# Grove_-_Tricks_v1_0.net
KiCad netlist of a schematic drawn in EAGLE
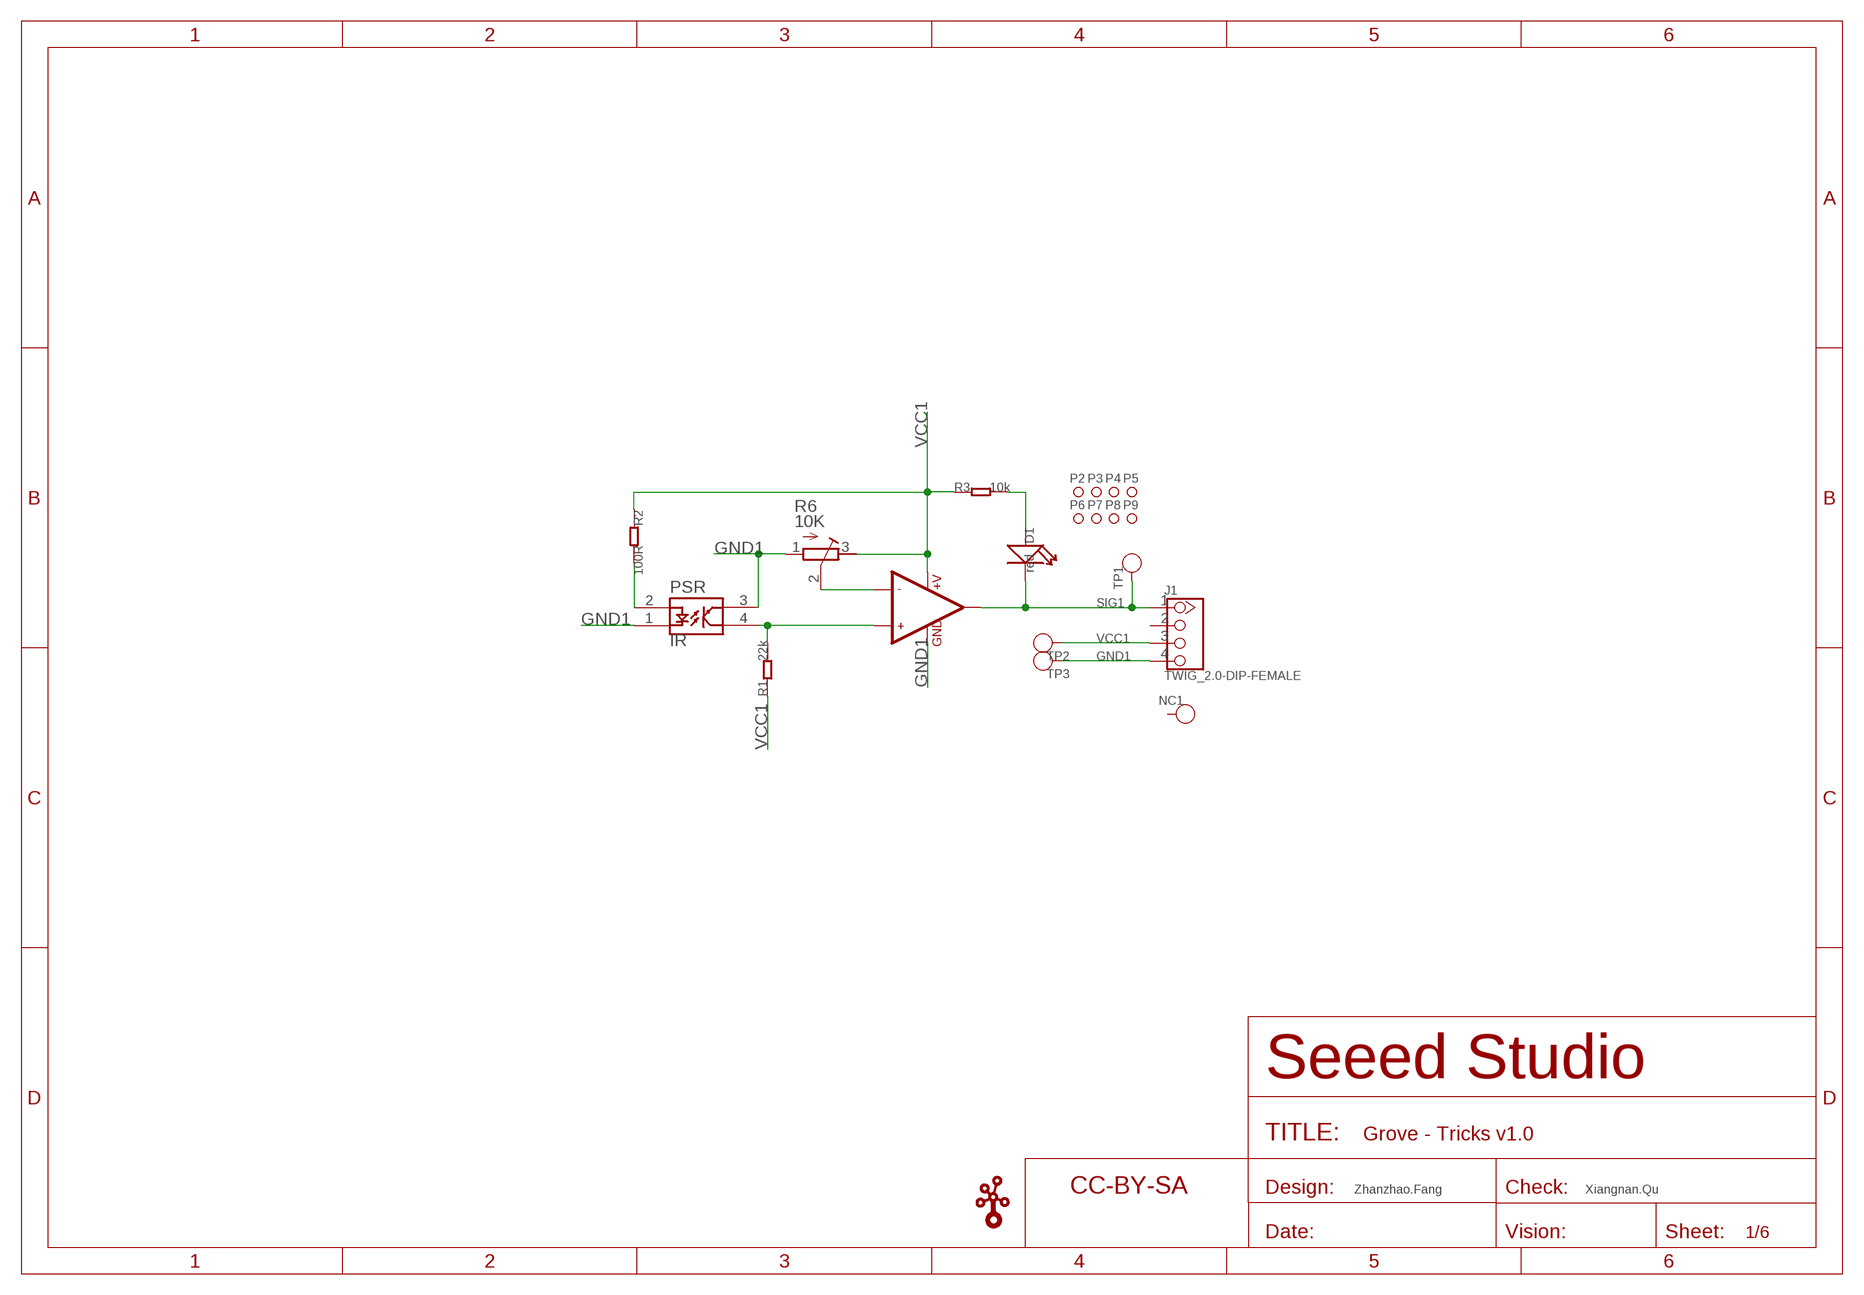
[diagram p0: schematic, sheet 1]
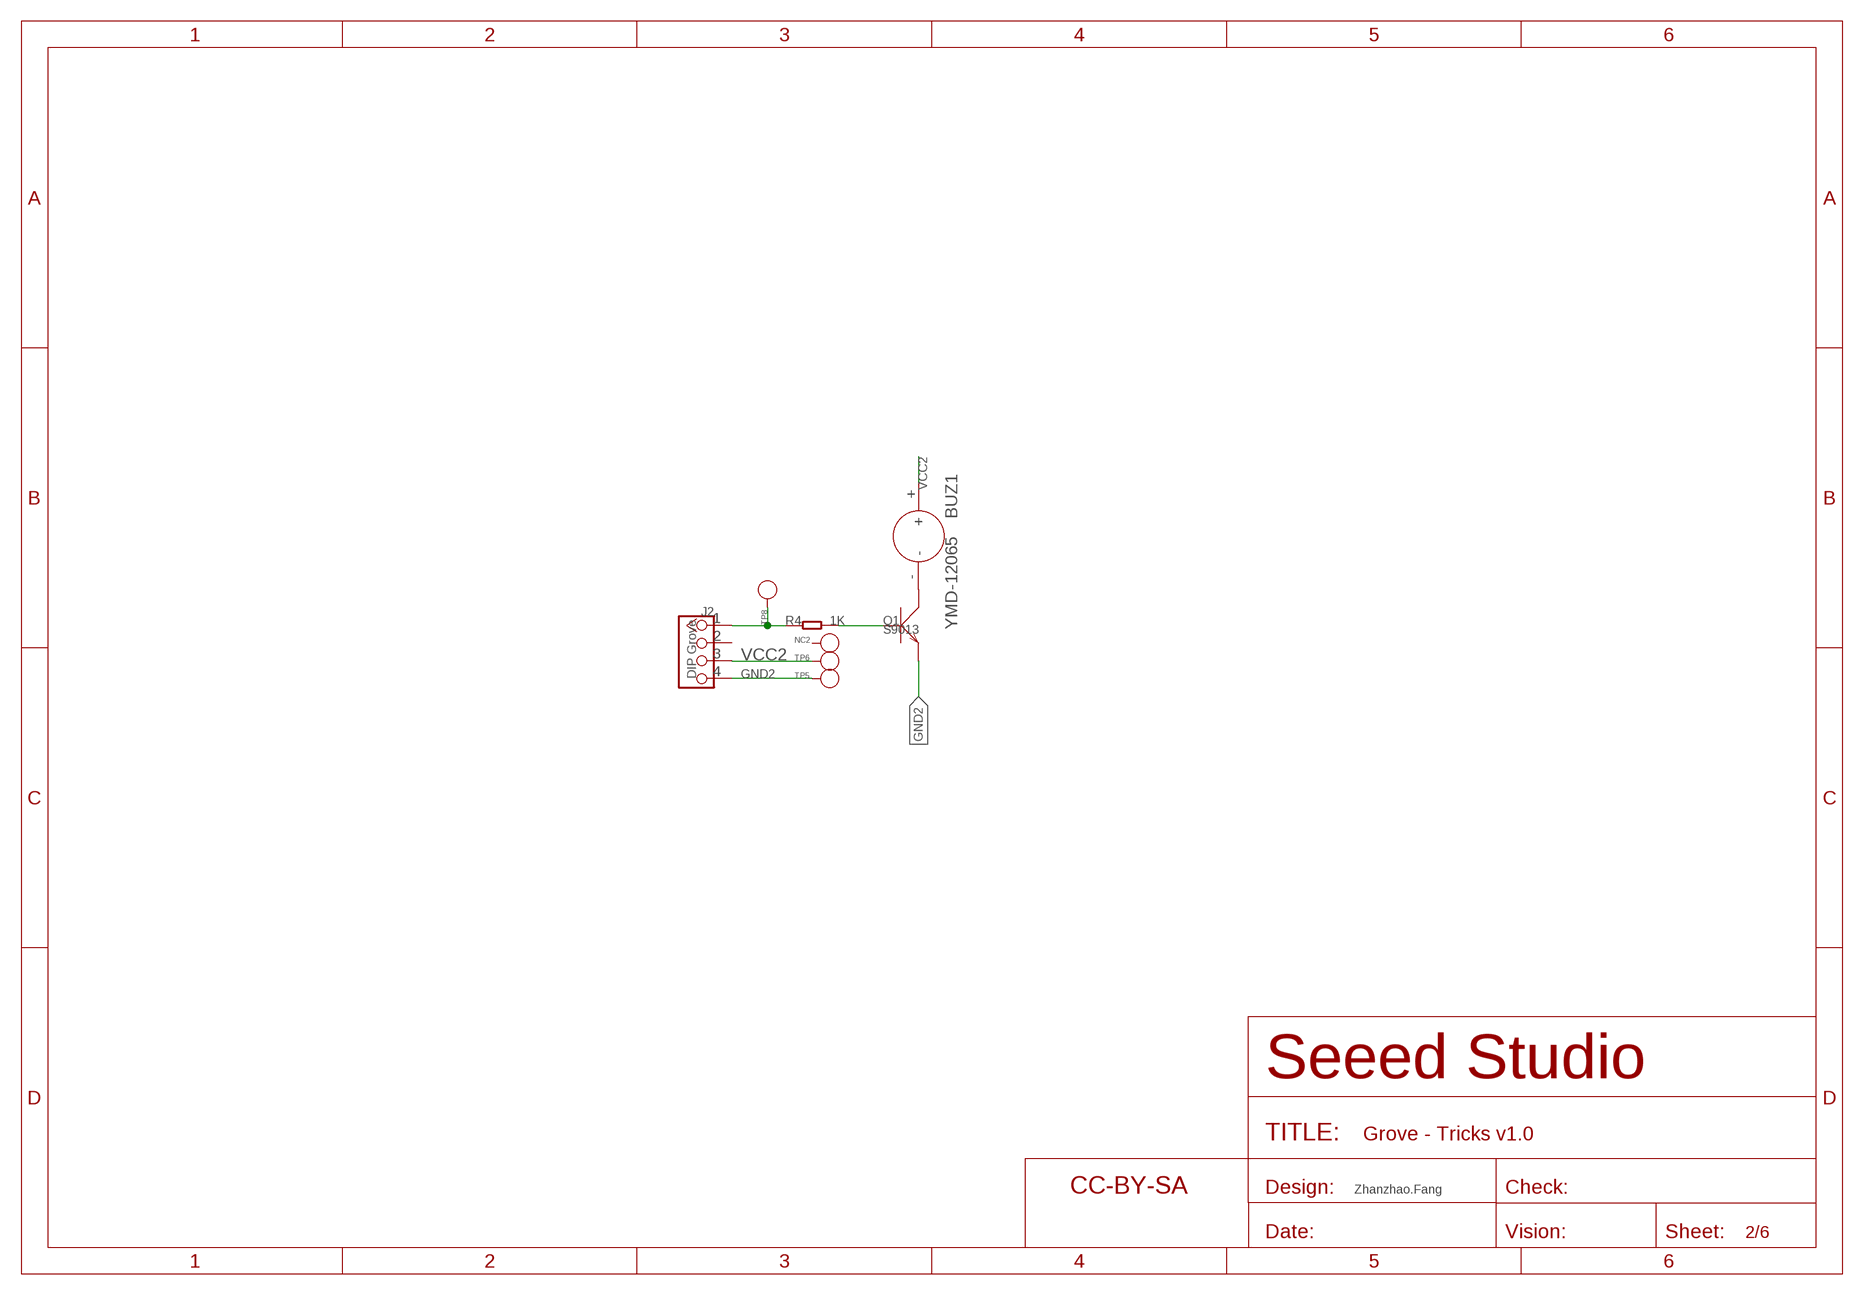
[diagram p1: schematic, sheet 2]
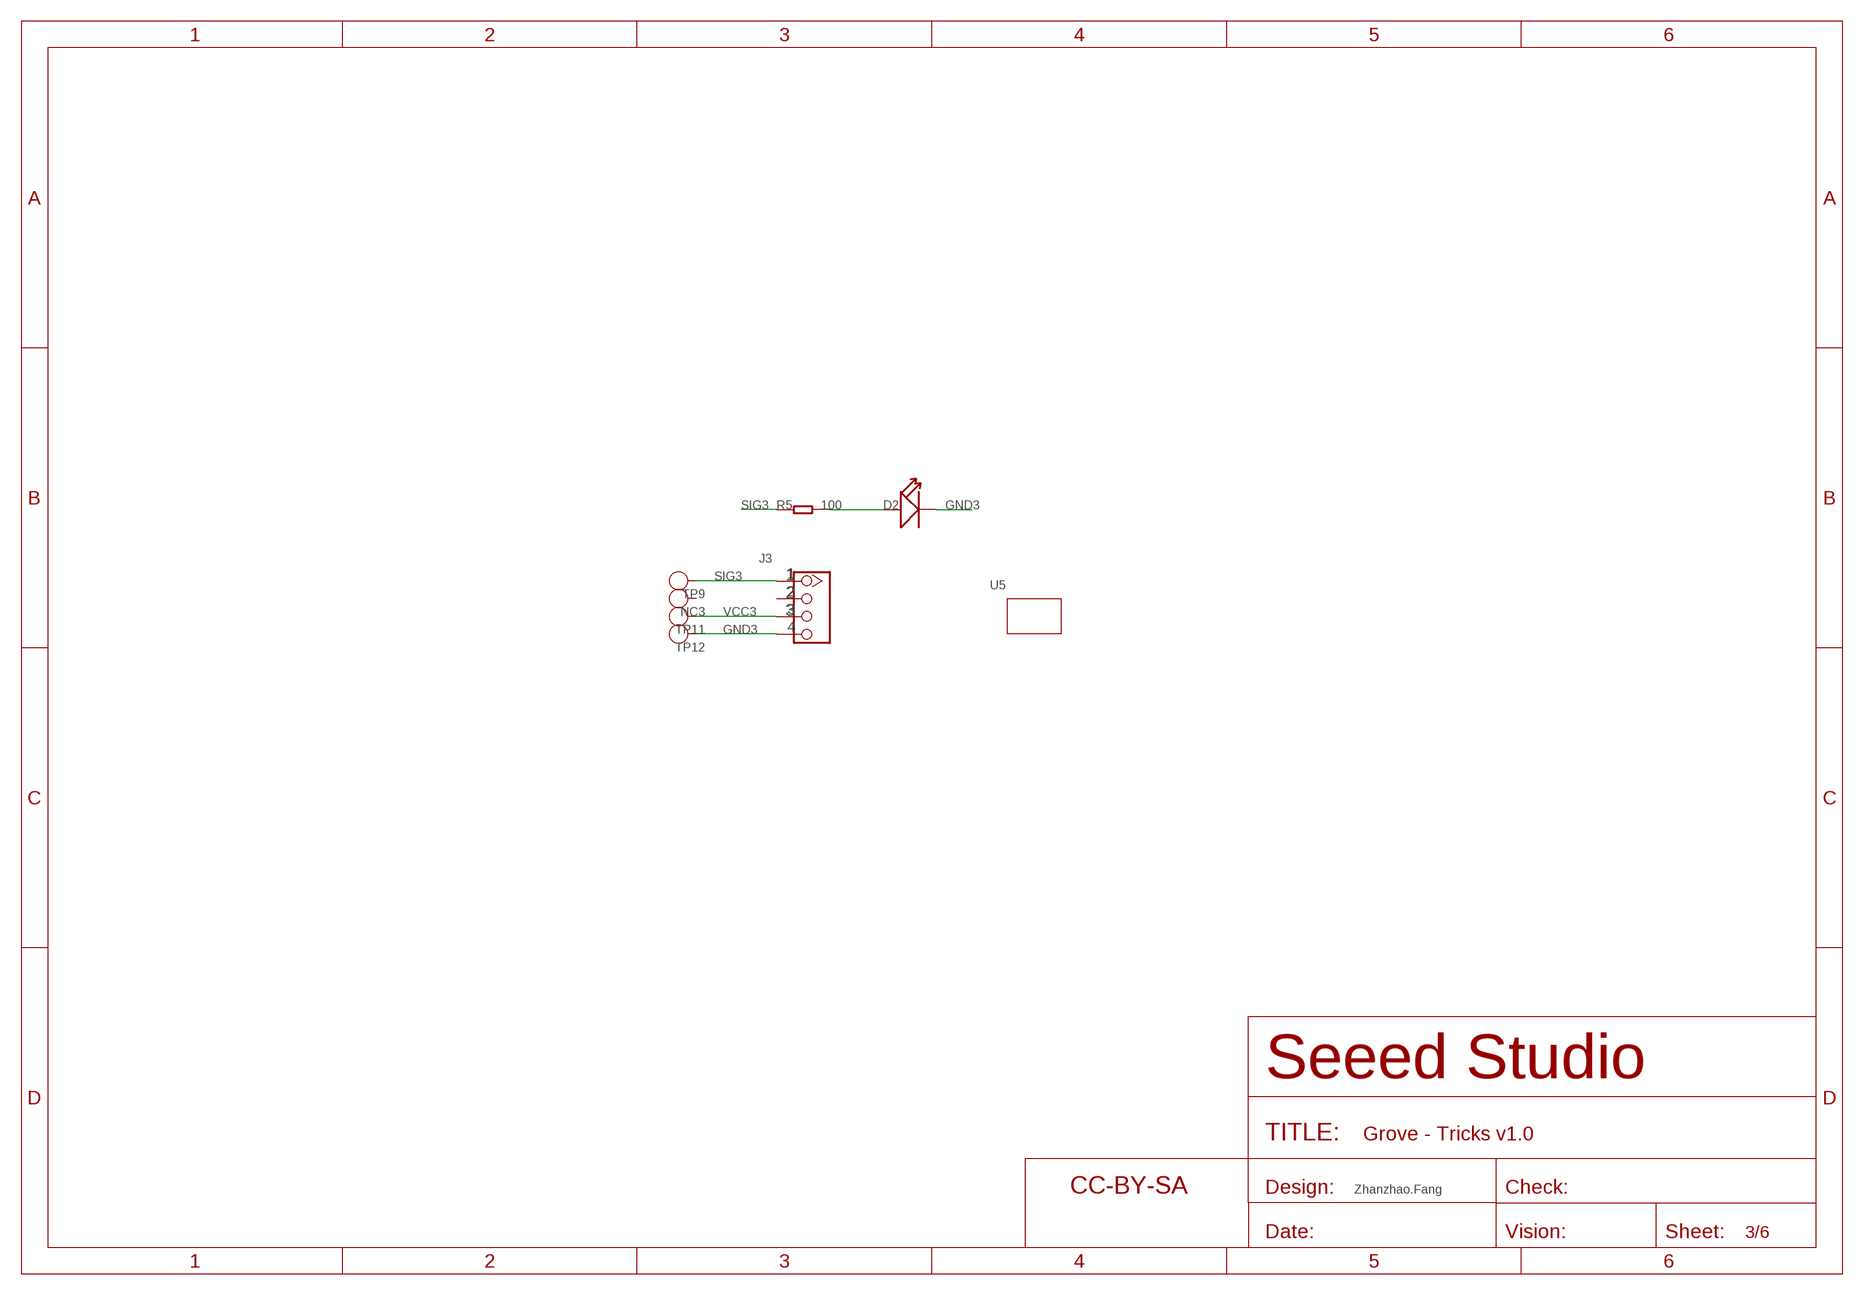
[diagram p2: schematic, sheet 3]
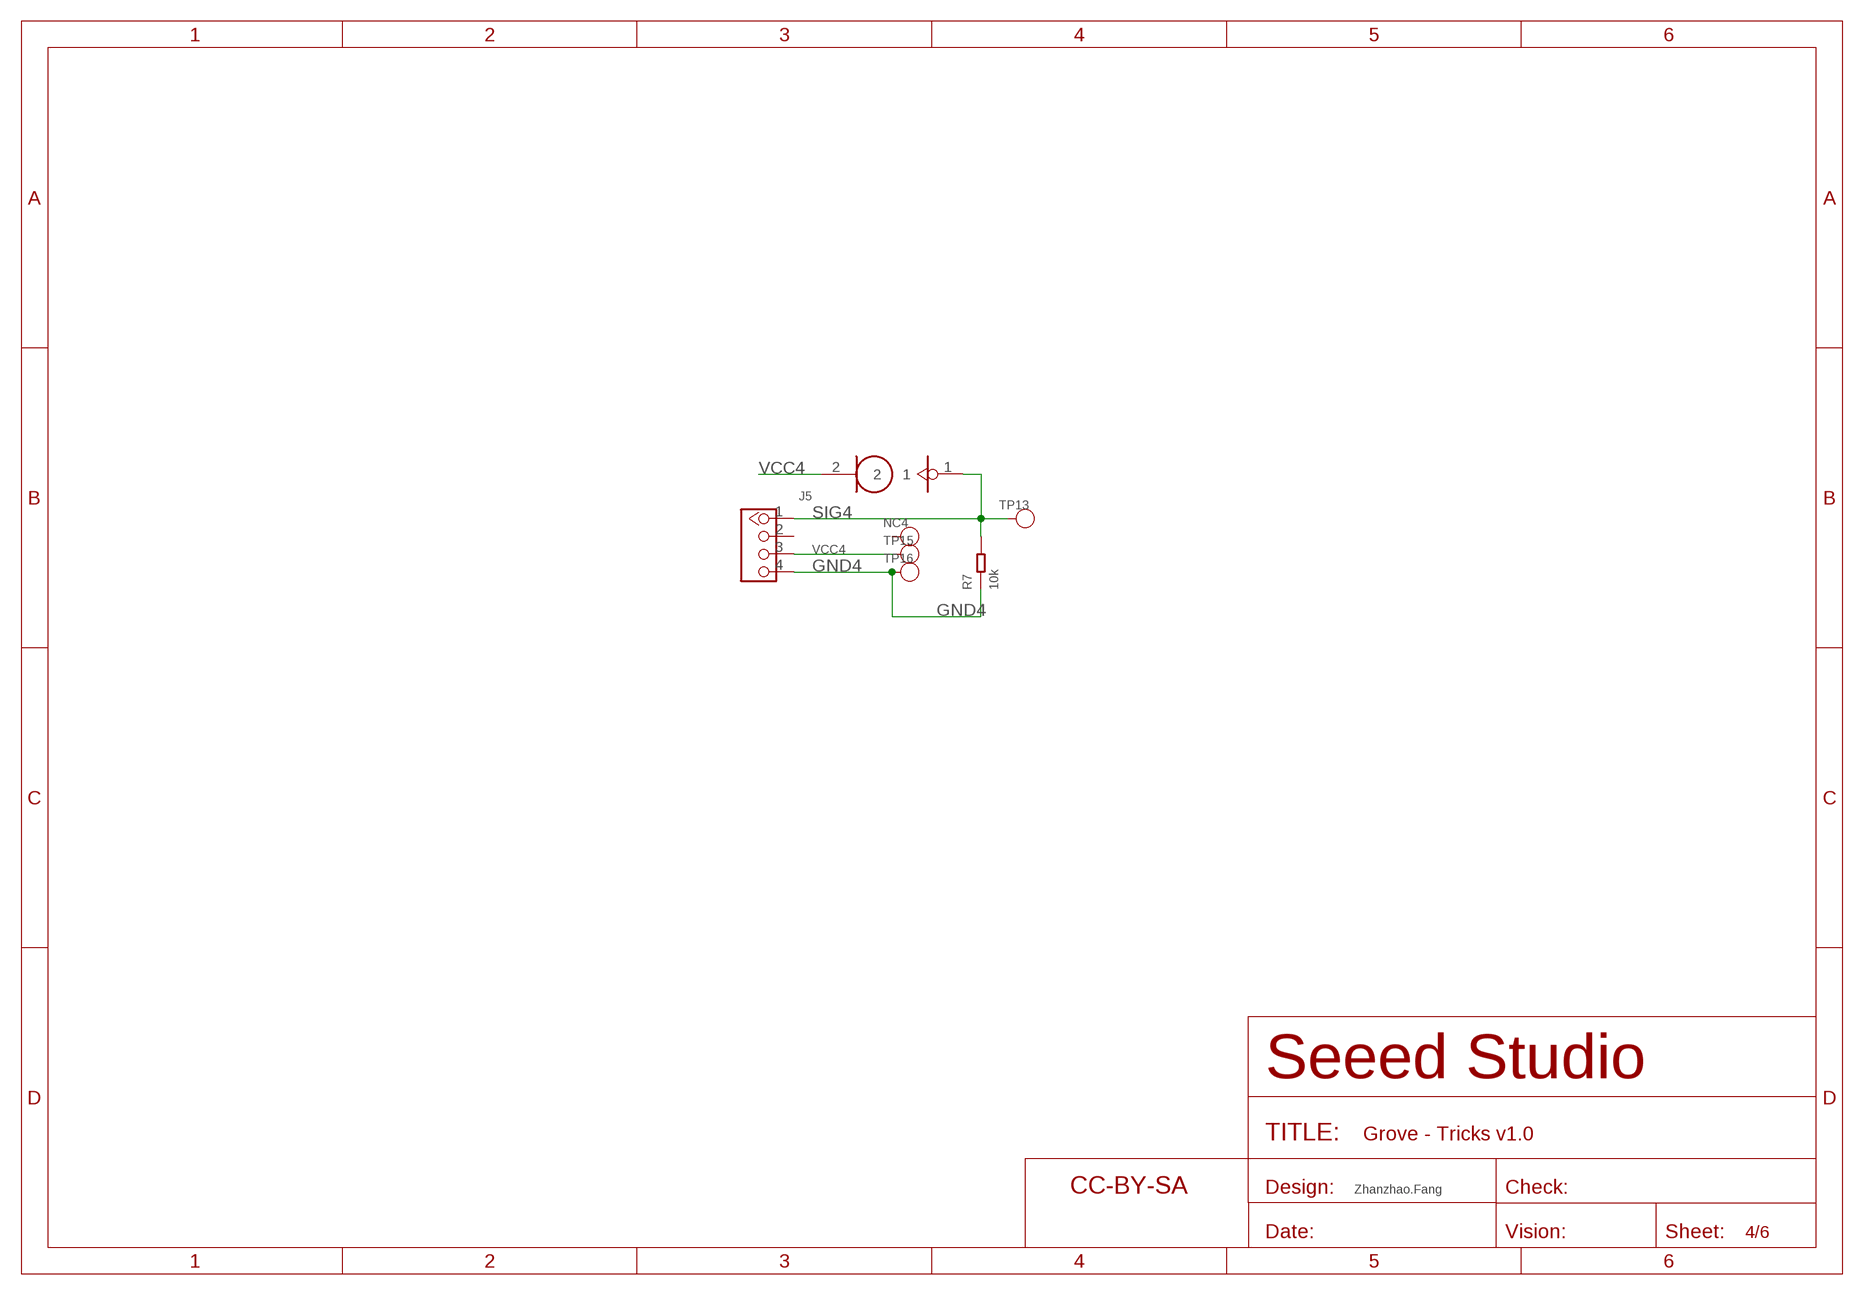
[diagram p3: schematic, sheet 4]
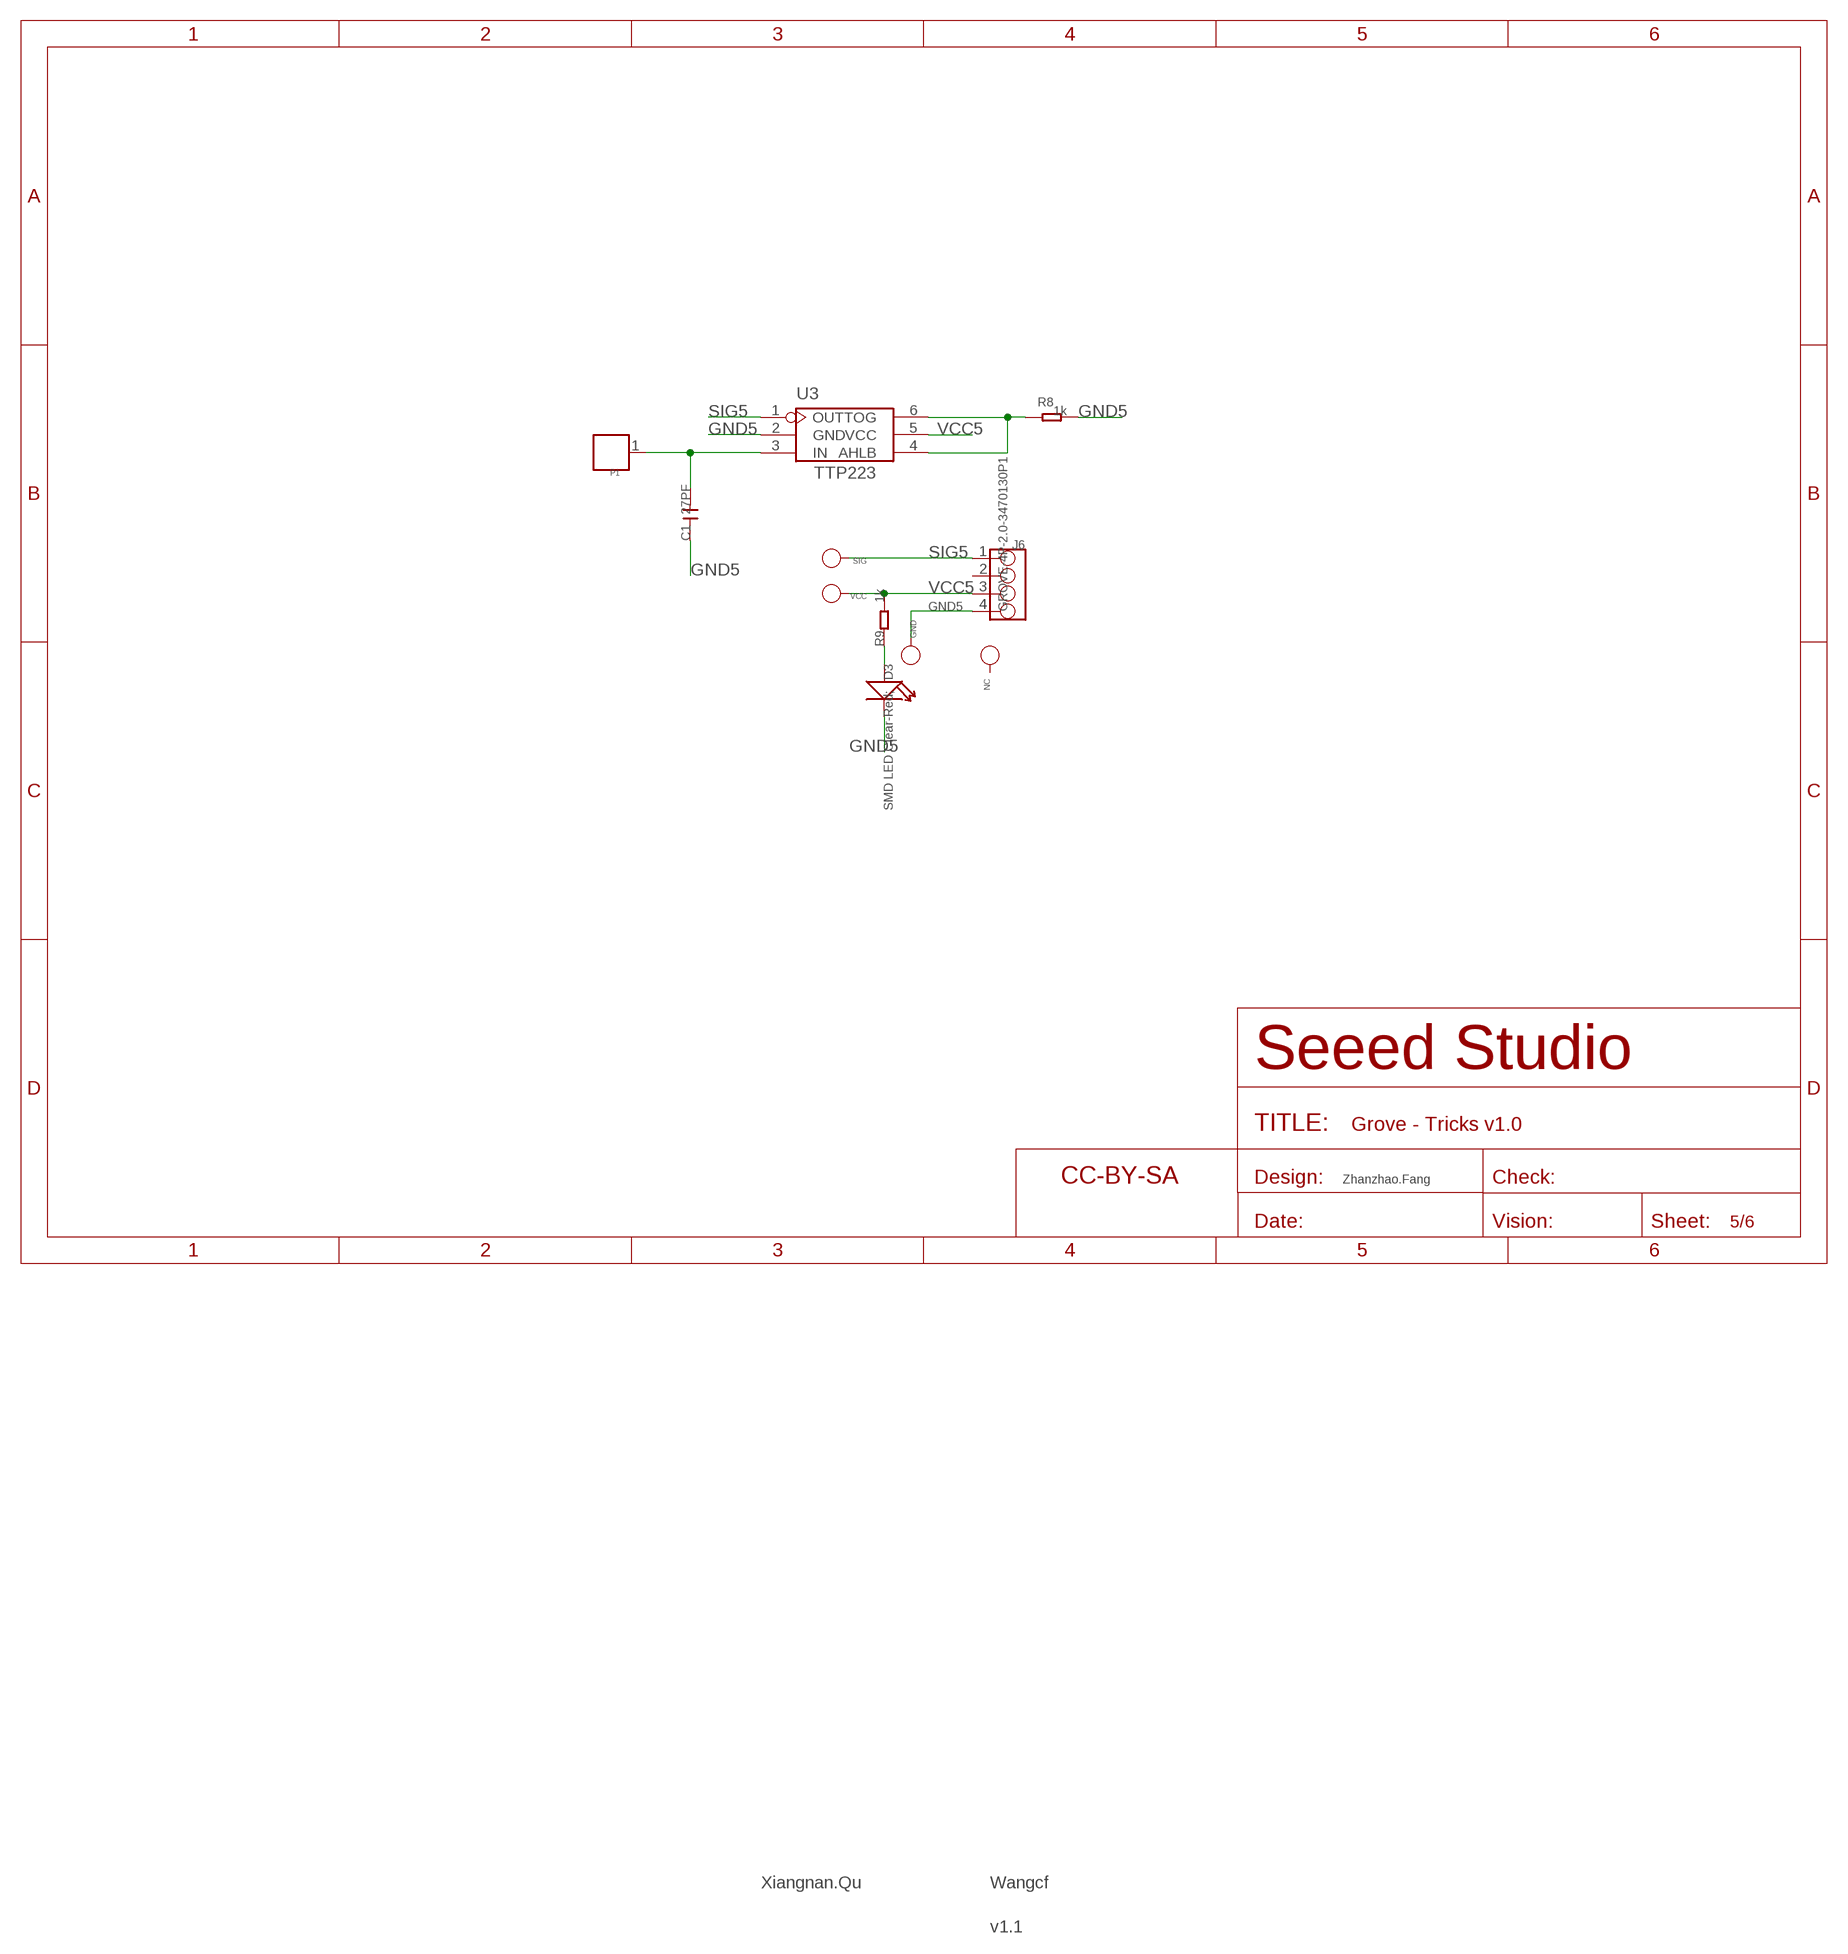
[diagram p4: schematic, sheet 5]
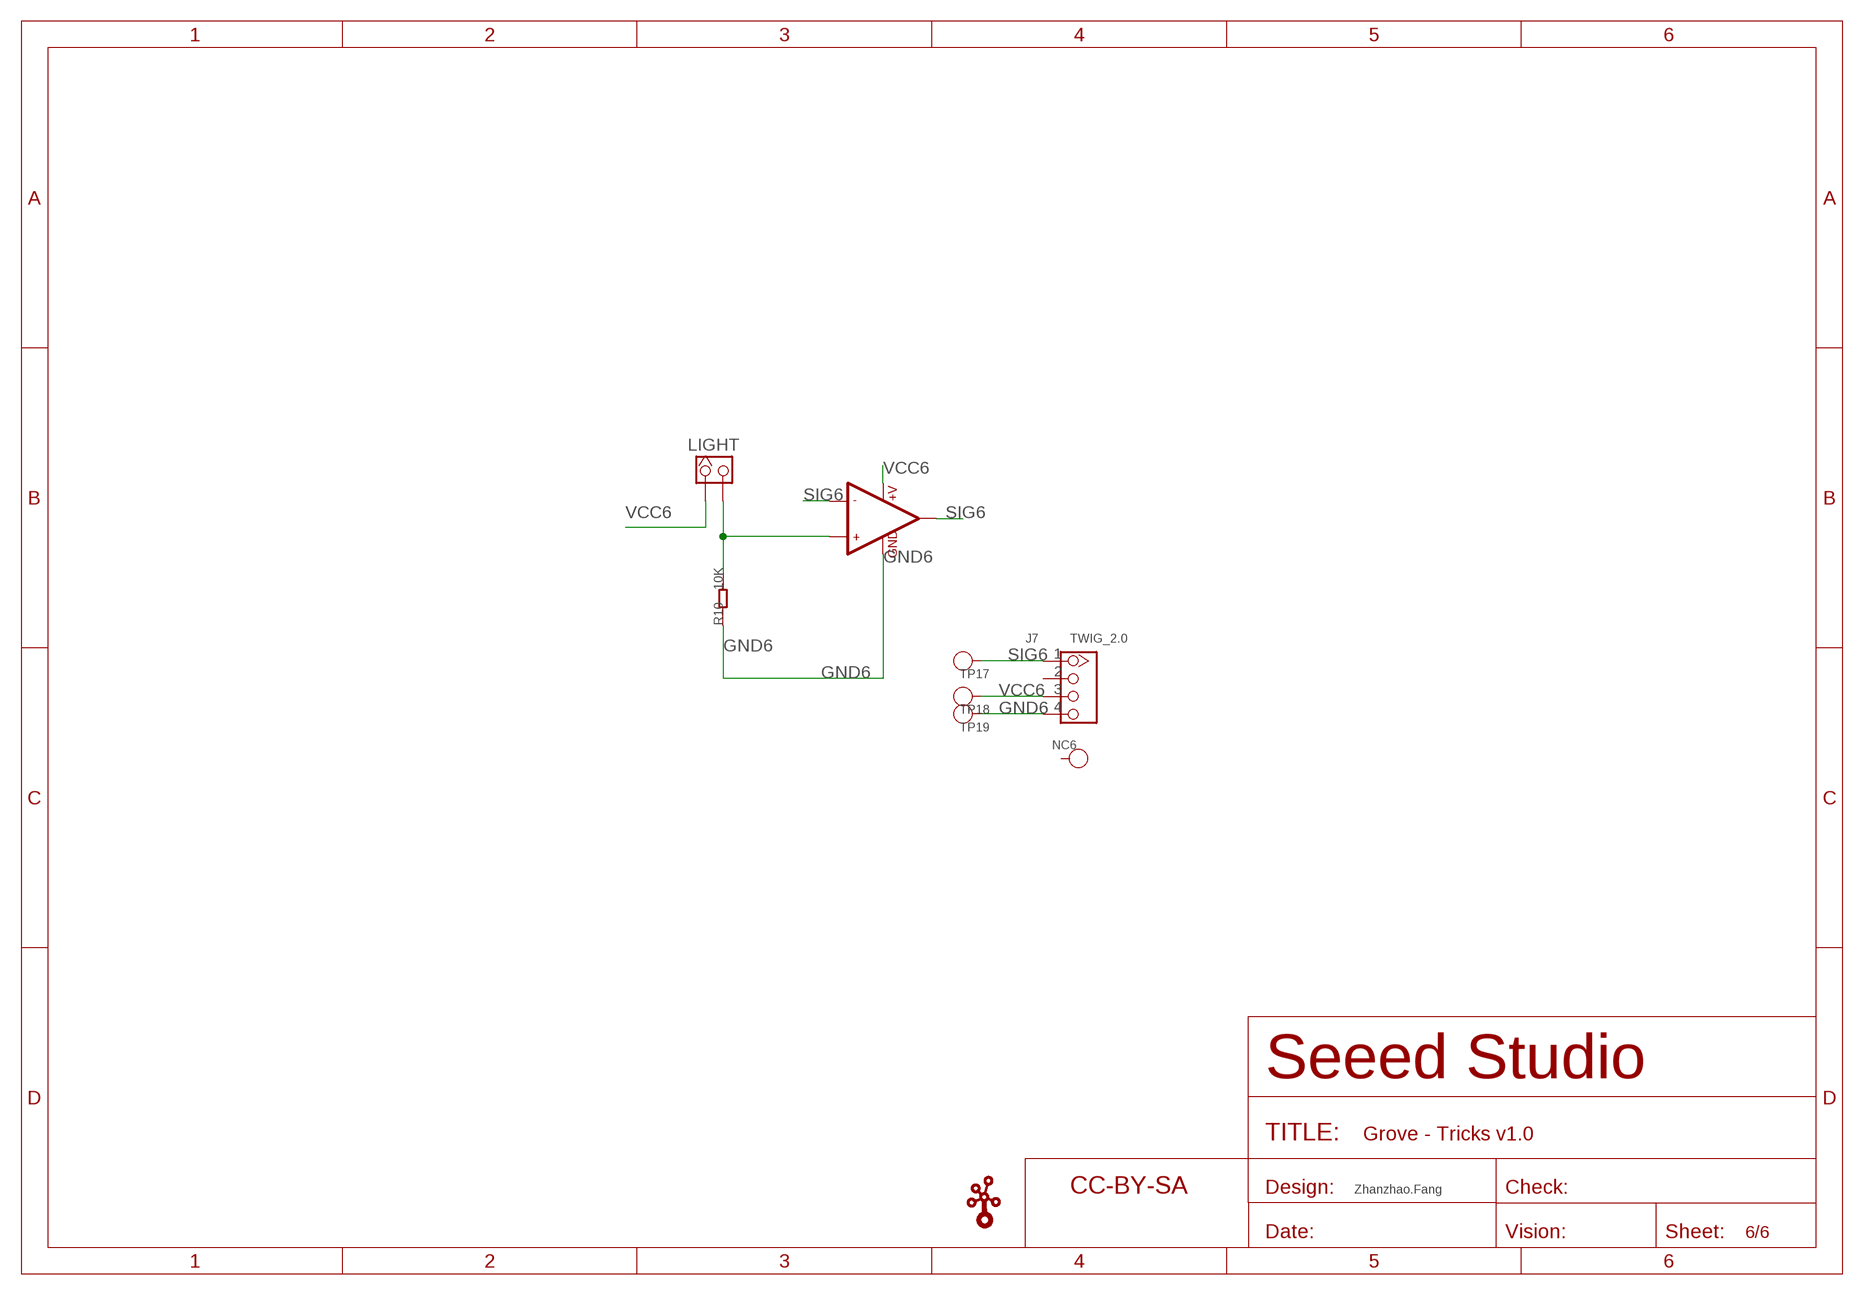
[diagram p5: schematic, sheet 6]

(export (version "E")
  (design (tool "Eeschema 10.0.6"))
  (components
    (comp (ref "BUZ1")
      (value "YMD-12065")
      (footprint "eagle-import:2P-7.6-D12X6.5H")
      (libsource (lib "eagle-import") (part "BUZZER-YMD12065"))
    )
    (comp (ref "J2")
      (value "DIP Grove")
      (footprint "eagle-import:4P-2.0")
      (libsource (lib "eagle-import") (part "TWIG-4P-2.0-2.0"))
    )
    (comp (ref "NC2")
      (value "PAD-TEST-POINT'4545'")
      (footprint "eagle-import:TP_4545")
      (fields (field (name "PARTNO") "DNP"))
      (libsource (lib "eagle-import") (part "PAD-TEST-POINT'4545'"))
    )
    (comp (ref "Q1")
      (value "S9013")
      (footprint "eagle-import:SOT23")
      (libsource (lib "eagle-import") (part "TRANSISTOR-NPN-SOT23"))
    )
    (comp (ref "R4")
      (value "1K")
      (footprint "eagle-import:R0603")
      (libsource (lib "eagle-import") (part "R-0603"))
    )
    (comp (ref "TP5")
      (value "PAD-TEST-POINT'4545'")
      (footprint "eagle-import:TP_4545")
      (fields (field (name "PARTNO") "DNP"))
      (libsource (lib "eagle-import") (part "PAD-TEST-POINT'4545'"))
    )
    (comp (ref "TP6")
      (value "PAD-TEST-POINT'4545'")
      (footprint "eagle-import:TP_4545")
      (fields (field (name "PARTNO") "DNP"))
      (libsource (lib "eagle-import") (part "PAD-TEST-POINT'4545'"))
    )
    (comp (ref "TP8")
      (value "PAD-TEST-POINT'4545'")
      (footprint "eagle-import:TP_4545")
      (fields (field (name "PARTNO") "DNP"))
      (libsource (lib "eagle-import") (part "PAD-TEST-POINT'4545'"))
    )
    (comp (ref "U$6")
      (value "SEEEDSTUDIO-OPEN-SCH-FRAME")
      (footprint "eagle-import:SEEEDSTUDIO-PCB-FRAME")
      (libsource (lib "eagle-import") (part "SEEEDSTUDIO-OPEN-SCH-FRAME"))
    )
    (comp (ref "C1")
      (value "27PF")
      (footprint "eagle-import:C0603")
      (libsource (lib "eagle-import") (part "C-0603"))
    )
    (comp (ref "D3")
      (value "SMD LED Clear-Red;")
      (footprint "eagle-import:LED-0603")
      (libsource (lib "eagle-import") (part "LED'0603'"))
    )
    (comp (ref "GND")
      (value "PAD-TEST-POINT'4545'")
      (footprint "eagle-import:TP_4545")
      (fields (field (name "PARTNO") "DNP"))
      (libsource (lib "eagle-import") (part "PAD-TEST-POINT'4545'"))
    )
    (comp (ref "J6")
      (value "GROVE-4P-2.0-3470130P1")
      (footprint "eagle-import:4P-2.0")
      (libsource (lib "eagle-import") (part "GROVE-4P-2.0-3470130P1"))
    )
    (comp (ref "NC")
      (value "PAD-TEST-POINT'4545'")
      (footprint "eagle-import:TP_4545")
      (fields (field (name "PARTNO") "DNP"))
      (libsource (lib "eagle-import") (part "PAD-TEST-POINT'4545'"))
    )
    (comp (ref "P1")
      (value "PAD'D450MIL'")
      (footprint "eagle-import:1P-D450")
      (libsource (lib "eagle-import") (part "PAD'D450MIL'"))
    )
    (comp (ref "R8")
      (value "1k")
      (footprint "eagle-import:R0603")
      (libsource (lib "eagle-import") (part "R-0603"))
    )
    (comp (ref "R9")
      (value "1k")
      (footprint "eagle-import:R0603")
      (libsource (lib "eagle-import") (part "R-0603"))
    )
    (comp (ref "SIG")
      (value "PAD-TEST-POINT'4545'")
      (footprint "eagle-import:TP_4545")
      (fields (field (name "PARTNO") "DNP"))
      (libsource (lib "eagle-import") (part "PAD-TEST-POINT'4545'"))
    )
    (comp (ref "U$12")
      (value "SEEEDSTUDIO-OPEN-SCH-FRAME")
      (footprint "eagle-import:SEEEDSTUDIO-PCB-FRAME")
      (libsource (lib "eagle-import") (part "SEEEDSTUDIO-OPEN-SCH-FRAME"))
    )
    (comp (ref "U3")
      (value "TTP223")
      (footprint "eagle-import:SOT23-6L")
      (libsource (lib "eagle-import") (part "TTP223"))
    )
    (comp (ref "VCC")
      (value "PAD-TEST-POINT'4545'")
      (footprint "eagle-import:TP_4545")
      (fields (field (name "PARTNO") "DNP"))
      (libsource (lib "eagle-import") (part "PAD-TEST-POINT'4545'"))
    )
    (comp (ref "D1")
      (value "red")
      (footprint "eagle-import:LED0603")
      (libsource (lib "eagle-import") (part "007-LED3540"))
    )
    (comp (ref "J1")
      (value "TWIG_2.0-DIP-FEMALE")
      (footprint "eagle-import:2.0_1X4")
      (libsource (lib "eagle-import") (part "TWIG_2.0-DIP-FEMALE"))
    )
    (comp (ref "NC1")
      (value "TEST-POINT'4545'")
      (footprint "eagle-import:TP-D45MIL")
      (fields (field (name "PARTNO") "DNP"))
      (libsource (lib "eagle-import") (part "TEST-POINT'4545'"))
    )
    (comp (ref "P2")
      (value "MARK-1.0'ANNULAR'")
      (footprint "eagle-import:ROUND-MARK-1.0")
      (fields (field (name "PARTNO") "DNP"))
      (libsource (lib "eagle-import") (part "MARK-1.0'ANNULAR'"))
    )
    (comp (ref "P3")
      (value "MARK-1.0'ANNULAR'")
      (footprint "eagle-import:ROUND-MARK-1.0")
      (fields (field (name "PARTNO") "DNP"))
      (libsource (lib "eagle-import") (part "MARK-1.0'ANNULAR'"))
    )
    (comp (ref "P4")
      (value "MARK-1.0'ANNULAR'")
      (footprint "eagle-import:ROUND-MARK-1.0")
      (fields (field (name "PARTNO") "DNP"))
      (libsource (lib "eagle-import") (part "MARK-1.0'ANNULAR'"))
    )
    (comp (ref "P5")
      (value "MARK-1.0'ANNULAR'")
      (footprint "eagle-import:ROUND-MARK-1.0")
      (fields (field (name "PARTNO") "DNP"))
      (libsource (lib "eagle-import") (part "MARK-1.0'ANNULAR'"))
    )
    (comp (ref "P6")
      (value "MARK-1.0'ANNULAR'")
      (footprint "eagle-import:ROUND-MARK-1.0")
      (fields (field (name "PARTNO") "DNP"))
      (libsource (lib "eagle-import") (part "MARK-1.0'ANNULAR'"))
    )
    (comp (ref "P7")
      (value "MARK-1.0'ANNULAR'")
      (footprint "eagle-import:ROUND-MARK-1.0")
      (fields (field (name "PARTNO") "DNP"))
      (libsource (lib "eagle-import") (part "MARK-1.0'ANNULAR'"))
    )
    (comp (ref "P8")
      (value "MARK-1.0'ANNULAR'")
      (footprint "eagle-import:ROUND-MARK-1.0")
      (fields (field (name "PARTNO") "DNP"))
      (libsource (lib "eagle-import") (part "MARK-1.0'ANNULAR'"))
    )
    (comp (ref "P9")
      (value "MARK-1.0'ANNULAR'")
      (footprint "eagle-import:ROUND-MARK-1.0")
      (fields (field (name "PARTNO") "DNP"))
      (libsource (lib "eagle-import") (part "MARK-1.0'ANNULAR'"))
    )
    (comp (ref "PSR")
      (value "PSR")
      (footprint "eagle-import:PSR")
      (libsource (lib "eagle-import") (part "PSR"))
    )
    (comp (ref "R1")
      (value "22k")
      (footprint "eagle-import:0603_S")
      (libsource (lib "eagle-import") (part "005-R0603_S"))
    )
    (comp (ref "R2")
      (value "100R")
      (footprint "eagle-import:0603_S")
      (libsource (lib "eagle-import") (part "005-R0603_S"))
    )
    (comp (ref "R3")
      (value "10k")
      (footprint "eagle-import:0603_S")
      (libsource (lib "eagle-import") (part "005-R0603_S"))
    )
    (comp (ref "R6")
      (value "10K")
      (footprint "eagle-import:RTRIM3214W")
      (libsource (lib "eagle-import") (part "R-TRIMM3214W"))
    )
    (comp (ref "TP1")
      (value "TEST-POINT'4545'")
      (footprint "eagle-import:TP-D45MIL")
      (fields (field (name "PARTNO") "DNP"))
      (libsource (lib "eagle-import") (part "TEST-POINT'4545'"))
    )
    (comp (ref "TP2")
      (value "TEST-POINT'4545'")
      (footprint "eagle-import:TP-D45MIL")
      (fields (field (name "PARTNO") "DNP"))
      (libsource (lib "eagle-import") (part "TEST-POINT'4545'"))
    )
    (comp (ref "TP3")
      (value "TEST-POINT'4545'")
      (footprint "eagle-import:TP-D45MIL")
      (fields (field (name "PARTNO") "DNP"))
      (libsource (lib "eagle-import") (part "TEST-POINT'4545'"))
    )
    (comp (ref "U$2")
      (value "TWIGLOGOTWIGLOGO_SMALL")
      (footprint "eagle-import:TWIGLOGO_SMALL")
      (libsource (lib "eagle-import") (part "TWIGLOGOTWIGLOGO_SMALL"))
    )
    (comp (ref "U$3")
      (value "SEEEDSTUDIO-OPEN-SCH-FRAME")
      (footprint "eagle-import:SEEEDSTUDIO-PCB-FRAME")
      (libsource (lib "eagle-import") (part "SEEEDSTUDIO-OPEN-SCH-FRAME"))
    )
    (comp (ref "U1")
      (value "002-LMV358")
      (footprint "eagle-import:SO08")
      (libsource (lib "eagle-import") (part "002-LMV358"))
    )
    (comp (ref "D2")
      (value "LED-3MM")
      (footprint "eagle-import:LED-2P-2.54-3MM")
      (libsource (lib "eagle-import") (part "LED-3MM"))
    )
    (comp (ref "J3")
      (value "GROVE-CONNECTOR-DIP-2.0")
      (footprint "eagle-import:HW4-2.0")
      (libsource (lib "eagle-import") (part "GROVE-CONNECTOR-DIP-2.0"))
    )
    (comp (ref "NC3")
      (value "TEST-POINT'4545'")
      (footprint "eagle-import:TP-D45MIL")
      (fields (field (name "PARTNO") "DNP"))
      (libsource (lib "eagle-import") (part "TEST-POINT'4545'"))
    )
    (comp (ref "R5")
      (value "100")
      (footprint "eagle-import:R1206")
      (libsource (lib "eagle-import") (part "R-1206"))
    )
    (comp (ref "TP9")
      (value "TEST-POINT'4545'")
      (footprint "eagle-import:TP-D45MIL")
      (fields (field (name "PARTNO") "DNP"))
      (libsource (lib "eagle-import") (part "TEST-POINT'4545'"))
    )
    (comp (ref "TP11")
      (value "TEST-POINT'4545'")
      (footprint "eagle-import:TP-D45MIL")
      (fields (field (name "PARTNO") "DNP"))
      (libsource (lib "eagle-import") (part "TEST-POINT'4545'"))
    )
    (comp (ref "TP12")
      (value "TEST-POINT'4545'")
      (footprint "eagle-import:TP-D45MIL")
      (fields (field (name "PARTNO") "DNP"))
      (libsource (lib "eagle-import") (part "TEST-POINT'4545'"))
    )
    (comp (ref "U$4")
      (value "SEEEDSTUDIO-OPEN-SCH-FRAME")
      (footprint "eagle-import:SEEEDSTUDIO-PCB-FRAME")
      (libsource (lib "eagle-import") (part "SEEEDSTUDIO-OPEN-SCH-FRAME"))
    )
    (comp (ref "U5")
      (value "GROVE")
      (footprint "eagle-import:GROVE-1_1-TEST-PLATFORM-LED")
      (libsource (lib "eagle-import") (part "GROVE"))
    )
    (comp (ref "J7")
      (value "TWIG_2.0")
      (footprint "eagle-import:HW4-2.0")
      (libsource (lib "eagle-import") (part "GROVE-CONNECTOR-DIP-2.0"))
    )
    (comp (ref "LIGHT")
      (value "HEADER_1X2_2.54")
      (footprint "eagle-import:CK_1_2")
      (libsource (lib "eagle-import") (part "HEADER_1X2_2.54"))
    )
    (comp (ref "NC6")
      (value "TEST-POINT'4545'")
      (footprint "eagle-import:TP-D45MIL")
      (fields (field (name "PARTNO") "DNP"))
      (libsource (lib "eagle-import") (part "TEST-POINT'4545'"))
    )
    (comp (ref "R10")
      (value "10K")
      (footprint "eagle-import:0603")
      (libsource (lib "eagle-import") (part "R0603"))
    )
    (comp (ref "TP17")
      (value "TEST-POINT'4545'")
      (footprint "eagle-import:TP-D45MIL")
      (fields (field (name "PARTNO") "DNP"))
      (libsource (lib "eagle-import") (part "TEST-POINT'4545'"))
    )
    (comp (ref "TP18")
      (value "TEST-POINT'4545'")
      (footprint "eagle-import:TP-D45MIL")
      (fields (field (name "PARTNO") "DNP"))
      (libsource (lib "eagle-import") (part "TEST-POINT'4545'"))
    )
    (comp (ref "TP19")
      (value "TEST-POINT'4545'")
      (footprint "eagle-import:TP-D45MIL")
      (fields (field (name "PARTNO") "DNP"))
      (libsource (lib "eagle-import") (part "TEST-POINT'4545'"))
    )
    (comp (ref "U$13")
      (value "SEEEDSTUDIO-OPEN-SCH-FRAME")
      (footprint "eagle-import:SEEEDSTUDIO-PCB-FRAME")
      (libsource (lib "eagle-import") (part "SEEEDSTUDIO-OPEN-SCH-FRAME"))
    )
    (comp (ref "U$16")
      (value "TWIGLOGOTWIGLOGO_SMALL")
      (footprint "eagle-import:TWIGLOGO_SMALL")
      (libsource (lib "eagle-import") (part "TWIGLOGOTWIGLOGO_SMALL"))
    )
    (comp (ref "U4")
      (value "LMV358")
      (footprint "eagle-import:SO08")
      (libsource (lib "eagle-import") (part "LMV358"))
    )
    (comp (ref "J4")
      (value "TILT")
      (footprint "eagle-import:TILT")
      (libsource (lib "eagle-import") (part "TILT"))
    )
    (comp (ref "J5")
      (value "GROVE-CONNECTOR-DIP-2.0")
      (footprint "eagle-import:HW4-2.0")
      (libsource (lib "eagle-import") (part "GROVE-CONNECTOR-DIP-2.0"))
    )
    (comp (ref "NC4")
      (value "TEST-POINT'4545'")
      (footprint "eagle-import:TP-D45MIL")
      (fields (field (name "PARTNO") "DNP"))
      (libsource (lib "eagle-import") (part "TEST-POINT'4545'"))
    )
    (comp (ref "R7")
      (value "10k")
      (footprint "eagle-import:R0603")
      (libsource (lib "eagle-import") (part "RES-0603"))
    )
    (comp (ref "TP13")
      (value "TEST-POINT'4545'")
      (footprint "eagle-import:TP-D45MIL")
      (fields (field (name "PARTNO") "DNP"))
      (libsource (lib "eagle-import") (part "TEST-POINT'4545'"))
    )
    (comp (ref "TP15")
      (value "TEST-POINT'4545'")
      (footprint "eagle-import:TP-D45MIL")
      (fields (field (name "PARTNO") "DNP"))
      (libsource (lib "eagle-import") (part "TEST-POINT'4545'"))
    )
    (comp (ref "TP16")
      (value "TEST-POINT'4545'")
      (footprint "eagle-import:TP-D45MIL")
      (fields (field (name "PARTNO") "DNP"))
      (libsource (lib "eagle-import") (part "TEST-POINT'4545'"))
    )
    (comp (ref "U$5")
      (value "SEEEDSTUDIO-OPEN-SCH-FRAME")
      (footprint "eagle-import:SEEEDSTUDIO-PCB-FRAME")
      (libsource (lib "eagle-import") (part "SEEEDSTUDIO-OPEN-SCH-FRAME"))
    )
  )
  (nets
    (net (code "1") (name "GND1") (class "Default")
      (node (ref "J1") (pin "4") (pinfunction "4_4") (pintype "bidirectional"))
      (node (ref "PSR") (pin "1") (pinfunction "1_1") (pintype "bidirectional"))
      (node (ref "PSR") (pin "3") (pinfunction "3_3") (pintype "bidirectional"))
      (node (ref "R6") (pin "1") (pinfunction "E_1") (pintype "passive"))
      (node (ref "TP3") (pin "T") (pinfunction "T_T") (pintype "bidirectional"))
      (node (ref "U1") (pin "4") (pinfunction "GND_4") (pintype "power_in"))
    )
    (net (code "2") (name "GND2") (class "Default")
      (node (ref "J2") (pin "4") (pinfunction "4_4") (pintype "bidirectional"))
      (node (ref "Q1") (pin "2") (pinfunction "E_2") (pintype "passive"))
      (node (ref "TP5") (pin "T") (pinfunction "T_T") (pintype "bidirectional"))
    )
    (net (code "3") (name "GND3") (class "Default")
      (node (ref "D2") (pin "K") (pinfunction "-_K") (pintype "passive"))
      (node (ref "J3") (pin "4") (pinfunction "4_4") (pintype "bidirectional"))
      (node (ref "TP12") (pin "T") (pinfunction "T_T") (pintype "bidirectional"))
    )
    (net (code "4") (name "GND4") (class "Default")
      (node (ref "J5") (pin "4") (pinfunction "4_4") (pintype "bidirectional"))
      (node (ref "R7") (pin "1") (pinfunction "1_1") (pintype "passive"))
      (node (ref "TP16") (pin "T") (pinfunction "T_T") (pintype "bidirectional"))
    )
    (net (code "5") (name "GND5") (class "Default")
      (node (ref "C1") (pin "1") (pinfunction "1_1") (pintype "passive"))
      (node (ref "D3") (pin "-") (pinfunction "-_-") (pintype "passive"))
      (node (ref "GND") (pin "T") (pinfunction "T_T") (pintype "bidirectional"))
      (node (ref "J6") (pin "4") (pinfunction "4_4") (pintype "bidirectional"))
      (node (ref "R8") (pin "2") (pinfunction "2_2") (pintype "passive"))
      (node (ref "U3") (pin "2") (pinfunction "GND_2") (pintype "bidirectional"))
    )
    (net (code "6") (name "GND6") (class "Default")
      (node (ref "J7") (pin "4") (pinfunction "4_4") (pintype "bidirectional"))
      (node (ref "R10") (pin "1") (pinfunction "1_1") (pintype "bidirectional"))
      (node (ref "TP19") (pin "T") (pinfunction "T_T") (pintype "bidirectional"))
      (node (ref "U4") (pin "4") (pinfunction "GND_4") (pintype "power_in"))
    )
    (net (code "7") (name "Net-(D1-+)") (class "Default")
      (node (ref "D1") (pin "1") (pinfunction "+_1") (pintype "passive"))
      (node (ref "R3") (pin "2") (pinfunction "2_2") (pintype "passive"))
    )
    (net (code "8") (name "Net-(D2-+)") (class "Default")
      (node (ref "D2") (pin "A") (pinfunction "+_A") (pintype "passive"))
      (node (ref "R5") (pin "2") (pinfunction "2_2") (pintype "passive"))
    )
    (net (code "9") (name "Net-(D3-Pad+)") (class "Default")
      (node (ref "D3") (pin "+") (pinfunction "+_+") (pintype "passive"))
      (node (ref "R9") (pin "1") (pinfunction "1_1") (pintype "passive"))
    )
    (net (code "10") (name "Net-(J2-Pad1)") (class "Default")
      (node (ref "J2") (pin "1") (pinfunction "1_1") (pintype "bidirectional"))
      (node (ref "R4") (pin "1") (pinfunction "1_1") (pintype "passive"))
      (node (ref "TP8") (pin "T") (pinfunction "T_T") (pintype "bidirectional"))
    )
    (net (code "11") (name "Net-(P1-P$1)") (class "Default")
      (node (ref "C1") (pin "2") (pinfunction "2_2") (pintype "passive"))
      (node (ref "P1") (pin "1") (pinfunction "P$1_1") (pintype "bidirectional"))
      (node (ref "U3") (pin "3") (pinfunction "IN_3") (pintype "bidirectional"))
    )
    (net (code "12") (name "Net-(PSR-Pad2)") (class "Default")
      (node (ref "PSR") (pin "2") (pinfunction "2_2") (pintype "bidirectional"))
      (node (ref "R2") (pin "2") (pinfunction "2_2") (pintype "passive"))
    )
    (net (code "13") (name "Net-(Q1-B)") (class "Default")
      (node (ref "Q1") (pin "1") (pinfunction "B_1") (pintype "passive"))
      (node (ref "R4") (pin "2") (pinfunction "2_2") (pintype "passive"))
    )
    (net (code "14") (name "Net-(Q1-C)") (class "Default")
      (node (ref "BUZ1") (pin "-") (pinfunction "-_-") (pintype "bidirectional"))
      (node (ref "Q1") (pin "3") (pinfunction "C_3") (pintype "passive"))
    )
    (net (code "15") (name "Net-(R6-S)") (class "Default")
      (node (ref "R6") (pin "2") (pinfunction "S_2") (pintype "passive"))
      (node (ref "U1") (pin "2") (pinfunction "-IN1_2") (pintype "input"))
    )
    (net (code "16") (name "Net-(U1A-+IN1)") (class "Default")
      (node (ref "PSR") (pin "4") (pinfunction "4_4") (pintype "bidirectional"))
      (node (ref "R1") (pin "2") (pinfunction "2_2") (pintype "passive"))
      (node (ref "U1") (pin "3") (pinfunction "+IN1_3") (pintype "input"))
    )
    (net (code "17") (name "Net-(U3-AHLB)") (class "Default")
      (node (ref "R8") (pin "1") (pinfunction "1_1") (pintype "passive"))
      (node (ref "U3") (pin "4") (pinfunction "AHLB_4") (pintype "bidirectional"))
      (node (ref "U3") (pin "6") (pinfunction "TOG_6") (pintype "bidirectional"))
    )
    (net (code "18") (name "Net-(U4A-+IN1)") (class "Default")
      (node (ref "LIGHT") (pin "2") (pinfunction "2_2") (pintype "bidirectional"))
      (node (ref "R10") (pin "2") (pinfunction "2_2") (pintype "bidirectional"))
      (node (ref "U4") (pin "3") (pinfunction "+IN1_3") (pintype "input"))
    )
    (net (code "19") (name "SIG1") (class "Default")
      (node (ref "D1") (pin "2") (pinfunction "-_2") (pintype "passive"))
      (node (ref "J1") (pin "1") (pinfunction "1_1") (pintype "bidirectional"))
      (node (ref "TP1") (pin "T") (pinfunction "T_T") (pintype "bidirectional"))
      (node (ref "U1") (pin "1") (pinfunction "OUT1_1") (pintype "output"))
    )
    (net (code "20") (name "SIG3") (class "Default")
      (node (ref "J3") (pin "1") (pinfunction "1_1") (pintype "bidirectional"))
      (node (ref "R5") (pin "1") (pinfunction "1_1") (pintype "passive"))
      (node (ref "TP9") (pin "T") (pinfunction "T_T") (pintype "bidirectional"))
    )
    (net (code "21") (name "SIG4") (class "Default")
      (node (ref "J4") (pin "1") (pinfunction "1_1") (pintype "bidirectional"))
      (node (ref "J5") (pin "1") (pinfunction "1_1") (pintype "bidirectional"))
      (node (ref "R7") (pin "2") (pinfunction "2_2") (pintype "passive"))
      (node (ref "TP13") (pin "T") (pinfunction "T_T") (pintype "bidirectional"))
    )
    (net (code "22") (name "SIG5") (class "Default")
      (node (ref "J6") (pin "1") (pinfunction "1_1") (pintype "bidirectional"))
      (node (ref "SIG") (pin "T") (pinfunction "T_T") (pintype "bidirectional"))
      (node (ref "U3") (pin "1") (pinfunction "OUT_1") (pintype "bidirectional"))
    )
    (net (code "23") (name "SIG6") (class "Default")
      (node (ref "J7") (pin "1") (pinfunction "1_1") (pintype "bidirectional"))
      (node (ref "TP17") (pin "T") (pinfunction "T_T") (pintype "bidirectional"))
      (node (ref "U4") (pin "1") (pinfunction "OUT1_1") (pintype "output"))
      (node (ref "U4") (pin "2") (pinfunction "-IN1_2") (pintype "input"))
    )
    (net (code "24") (name "VCC1") (class "Default")
      (node (ref "J1") (pin "3") (pinfunction "3_3") (pintype "bidirectional"))
      (node (ref "R1") (pin "1") (pinfunction "1_1") (pintype "passive"))
      (node (ref "R2") (pin "1") (pinfunction "1_1") (pintype "passive"))
      (node (ref "R3") (pin "1") (pinfunction "1_1") (pintype "passive"))
      (node (ref "R6") (pin "3") (pinfunction "A_3") (pintype "passive"))
      (node (ref "TP2") (pin "T") (pinfunction "T_T") (pintype "bidirectional"))
      (node (ref "U1") (pin "8") (pinfunction "+V_8") (pintype "power_in"))
    )
    (net (code "25") (name "VCC2") (class "Default")
      (node (ref "BUZ1") (pin "+") (pinfunction "+_+") (pintype "bidirectional"))
      (node (ref "J2") (pin "3") (pinfunction "3_3") (pintype "bidirectional"))
      (node (ref "TP6") (pin "T") (pinfunction "T_T") (pintype "bidirectional"))
    )
    (net (code "26") (name "VCC3") (class "Default")
      (node (ref "J3") (pin "3") (pinfunction "3_3") (pintype "bidirectional"))
      (node (ref "TP11") (pin "T") (pinfunction "T_T") (pintype "bidirectional"))
    )
    (net (code "27") (name "VCC4") (class "Default")
      (node (ref "J4") (pin "2") (pinfunction "2_2") (pintype "bidirectional"))
      (node (ref "J5") (pin "3") (pinfunction "3_3") (pintype "bidirectional"))
      (node (ref "TP15") (pin "T") (pinfunction "T_T") (pintype "bidirectional"))
    )
    (net (code "28") (name "VCC5") (class "Default")
      (node (ref "J6") (pin "3") (pinfunction "3_3") (pintype "bidirectional"))
      (node (ref "R9") (pin "2") (pinfunction "2_2") (pintype "passive"))
      (node (ref "U3") (pin "5") (pinfunction "VCC_5") (pintype "bidirectional"))
      (node (ref "VCC") (pin "T") (pinfunction "T_T") (pintype "bidirectional"))
    )
    (net (code "29") (name "VCC6") (class "Default")
      (node (ref "J7") (pin "3") (pinfunction "3_3") (pintype "bidirectional"))
      (node (ref "LIGHT") (pin "1") (pinfunction "1_1") (pintype "bidirectional"))
      (node (ref "TP18") (pin "T") (pinfunction "T_T") (pintype "bidirectional"))
      (node (ref "U4") (pin "8") (pinfunction "+V_8") (pintype "power_in"))
    )
    (net (code "30") (name "unconnected-(J1-Pad2)") (class "Default")
      (node (ref "J1") (pin "2") (pinfunction "2_2") (pintype "bidirectional"))
    )
    (net (code "31") (name "unconnected-(J2-Pad2)") (class "Default")
      (node (ref "J2") (pin "2") (pinfunction "2_2") (pintype "bidirectional"))
    )
    (net (code "32") (name "unconnected-(J3-Pad2)") (class "Default")
      (node (ref "J3") (pin "2") (pinfunction "2_2") (pintype "bidirectional"))
    )
    (net (code "33") (name "unconnected-(J5-Pad2)") (class "Default")
      (node (ref "J5") (pin "2") (pinfunction "2_2") (pintype "bidirectional"))
    )
    (net (code "34") (name "unconnected-(J6-Pad2)") (class "Default")
      (node (ref "J6") (pin "2") (pinfunction "2_2") (pintype "bidirectional"))
    )
    (net (code "35") (name "unconnected-(J7-Pad2)") (class "Default")
      (node (ref "J7") (pin "2") (pinfunction "2_2") (pintype "bidirectional"))
    )
    (net (code "36") (name "unconnected-(NC-PadT)") (class "Default")
      (node (ref "NC") (pin "T") (pinfunction "T_T") (pintype "bidirectional"))
    )
    (net (code "37") (name "unconnected-(NC1-PadT)") (class "Default")
      (node (ref "NC1") (pin "T") (pinfunction "T_T") (pintype "bidirectional"))
    )
    (net (code "38") (name "unconnected-(NC2-PadT)") (class "Default")
      (node (ref "NC2") (pin "T") (pinfunction "T_T") (pintype "bidirectional"))
    )
    (net (code "39") (name "unconnected-(NC3-PadT)") (class "Default")
      (node (ref "NC3") (pin "T") (pinfunction "T_T") (pintype "bidirectional"))
    )
    (net (code "40") (name "unconnected-(NC4-PadT)") (class "Default")
      (node (ref "NC4") (pin "T") (pinfunction "T_T") (pintype "bidirectional"))
    )
    (net (code "41") (name "unconnected-(NC6-PadT)") (class "Default")
      (node (ref "NC6") (pin "T") (pinfunction "T_T") (pintype "bidirectional"))
    )
  )
)
